# EXM_Relay_Three_-_Rev_A1.net
KiCad netlist of a schematic drawn in EAGLE
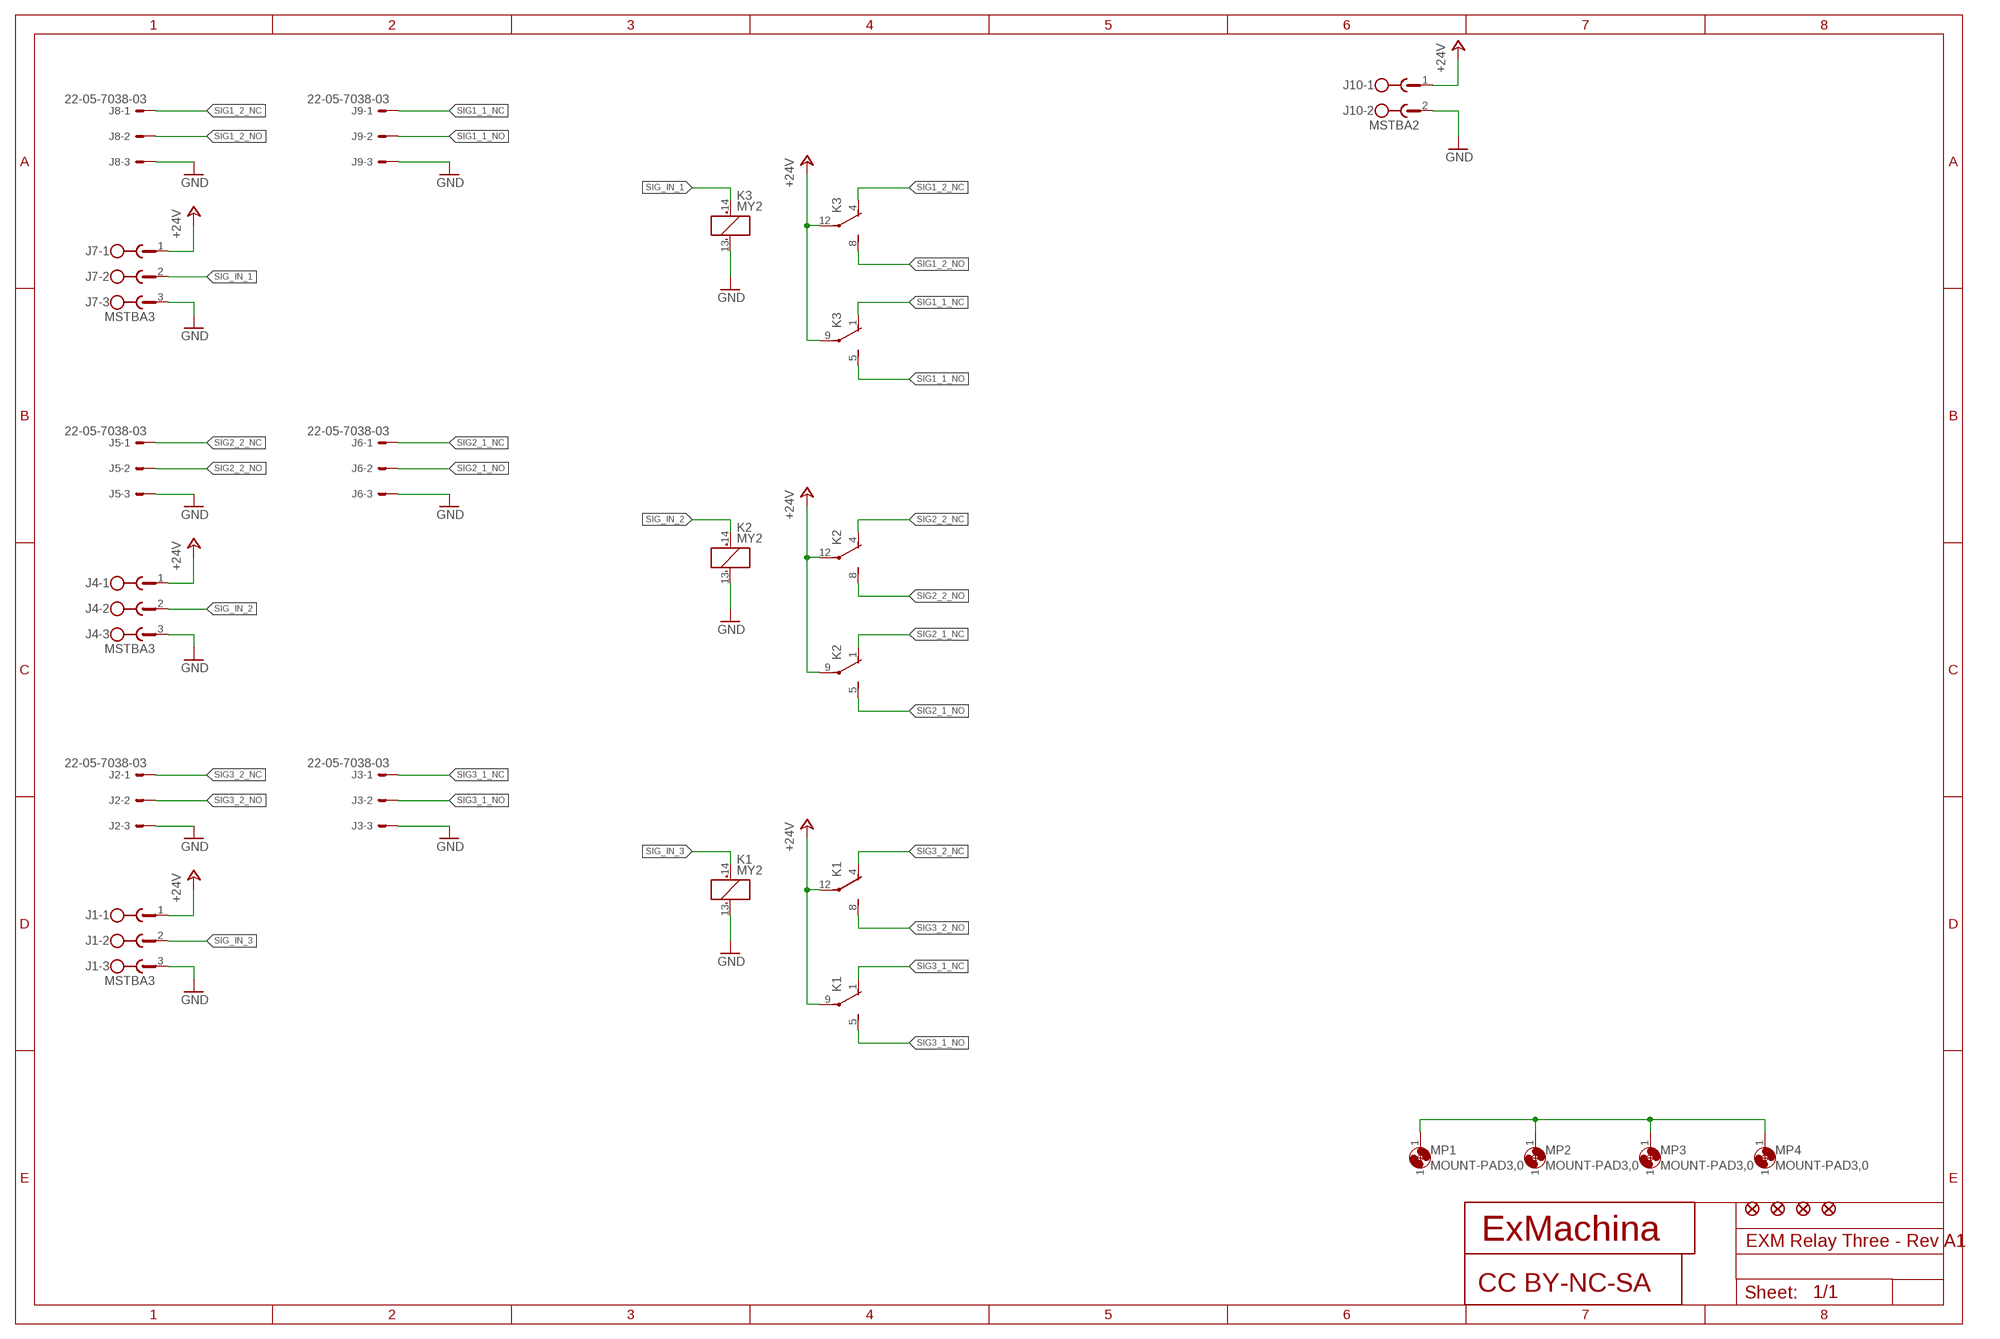
[diagram p0: schematic, sheet 1]

(export (version "E")
  (design (tool "Eeschema 10.0.6"))
  (components
    (comp (ref "CC1")
      (value "CC-BY-NC-SA")
      (footprint "eagle-import:CC-BY-NC-SA")
      (libsource (lib "eagle-import") (part "CC-BY-NC-SA"))
    )
    (comp (ref "J1")
      (value "MSTBA3")
      (footprint "eagle-import:MSTBA3")
      (fields (field (name "MF") "FARNELL") (field (name "MPN") "1757255"))
      (libsource (lib "eagle-import") (part "MSTBA3"))
    )
    (comp (ref "J2")
      (value "22-05-7038-03")
      (footprint "eagle-import:7395-03")
      (fields (field (name "MPN") "22-05-7038") (field (name "OC_NEWARK") "26M6362"))
      (libsource (lib "eagle-import") (part "22-?-0305-7038"))
    )
    (comp (ref "J3")
      (value "22-05-7038-03")
      (footprint "eagle-import:7395-03")
      (fields (field (name "MPN") "22-05-7038") (field (name "OC_NEWARK") "26M6362"))
      (libsource (lib "eagle-import") (part "22-?-0305-7038"))
    )
    (comp (ref "J4")
      (value "MSTBA3")
      (footprint "eagle-import:MSTBA3")
      (fields (field (name "MF") "FARNELL") (field (name "MPN") "1757255"))
      (libsource (lib "eagle-import") (part "MSTBA3"))
    )
    (comp (ref "J5")
      (value "22-05-7038-03")
      (footprint "eagle-import:7395-03")
      (fields (field (name "MPN") "22-05-7038") (field (name "OC_NEWARK") "26M6362"))
      (libsource (lib "eagle-import") (part "22-?-0305-7038"))
    )
    (comp (ref "J6")
      (value "22-05-7038-03")
      (footprint "eagle-import:7395-03")
      (fields (field (name "MPN") "22-05-7038") (field (name "OC_NEWARK") "26M6362"))
      (libsource (lib "eagle-import") (part "22-?-0305-7038"))
    )
    (comp (ref "J7")
      (value "MSTBA3")
      (footprint "eagle-import:MSTBA3")
      (fields (field (name "MF") "FARNELL") (field (name "MPN") "1757255"))
      (libsource (lib "eagle-import") (part "MSTBA3"))
    )
    (comp (ref "J8")
      (value "22-05-7038-03")
      (footprint "eagle-import:7395-03")
      (fields (field (name "MPN") "22-05-7038") (field (name "OC_NEWARK") "26M6362"))
      (libsource (lib "eagle-import") (part "22-?-0305-7038"))
    )
    (comp (ref "J9")
      (value "22-05-7038-03")
      (footprint "eagle-import:7395-03")
      (fields (field (name "MPN") "22-05-7038") (field (name "OC_NEWARK") "26M6362"))
      (libsource (lib "eagle-import") (part "22-?-0305-7038"))
    )
    (comp (ref "J10")
      (value "MSTBA2")
      (footprint "eagle-import:MSTBA2")
      (fields (field (name "MF") "FARNELL") (field (name "MPN") "1757242"))
      (libsource (lib "eagle-import") (part "MSTBA2"))
    )
    (comp (ref "JP1")
      (value "FIDUCIAL1X2")
      (footprint "eagle-import:FIDUCIAL-1X2")
      (libsource (lib "eagle-import") (part "FIDUCIAL1X2"))
    )
    (comp (ref "JP2")
      (value "FIDUCIAL1X2")
      (footprint "eagle-import:FIDUCIAL-1X2")
      (libsource (lib "eagle-import") (part "FIDUCIAL1X2"))
    )
    (comp (ref "JP3")
      (value "FIDUCIAL1X2")
      (footprint "eagle-import:FIDUCIAL-1X2")
      (libsource (lib "eagle-import") (part "FIDUCIAL1X2"))
    )
    (comp (ref "JP4")
      (value "FIDUCIAL1X2")
      (footprint "eagle-import:FIDUCIAL-1X2")
      (libsource (lib "eagle-import") (part "FIDUCIAL1X2"))
    )
    (comp (ref "K1")
      (value "MY2")
      (footprint "eagle-import:PY08")
      (fields
        (field (name "MF") "OMRON COMPONENTS USA")
        (field (name "MPN") "PY08")
        (field (name "OC_NEWARK") "36K3464")
      )
      (libsource (lib "eagle-import") (part "MY2"))
    )
    (comp (ref "K2")
      (value "MY2")
      (footprint "eagle-import:PY08")
      (fields
        (field (name "MF") "OMRON COMPONENTS USA")
        (field (name "MPN") "PY08")
        (field (name "OC_NEWARK") "36K3464")
      )
      (libsource (lib "eagle-import") (part "MY2"))
    )
    (comp (ref "K3")
      (value "MY2")
      (footprint "eagle-import:PY08")
      (fields
        (field (name "MF") "OMRON COMPONENTS USA")
        (field (name "MPN") "PY08")
        (field (name "OC_NEWARK") "36K3464")
      )
      (libsource (lib "eagle-import") (part "MY2"))
    )
    (comp (ref "MP1")
      (value "MOUNT-PAD3,0")
      (footprint "eagle-import:P3,0")
      (libsource (lib "eagle-import") (part "MOUNT-PAD3,0"))
    )
    (comp (ref "MP2")
      (value "MOUNT-PAD3,0")
      (footprint "eagle-import:P3,0")
      (libsource (lib "eagle-import") (part "MOUNT-PAD3,0"))
    )
    (comp (ref "MP3")
      (value "MOUNT-PAD3,0")
      (footprint "eagle-import:P3,0")
      (libsource (lib "eagle-import") (part "MOUNT-PAD3,0"))
    )
    (comp (ref "MP4")
      (value "MOUNT-PAD3,0")
      (footprint "eagle-import:P3,0")
      (libsource (lib "eagle-import") (part "MOUNT-PAD3,0"))
    )
    (comp (ref "T1")
      (value "EXMACHINA-LOGO-NAME")
      (footprint "eagle-import:EXM-LOGO-BASELINE")
      (libsource (lib "eagle-import") (part "EXMACHINA-LOGO-NAME"))
    )
  )
  (nets
    (net (code "1") (name "+24V") (class "Default")
      (node (ref "J1") (pin "1") (pinfunction "1_1") (pintype "passive"))
      (node (ref "J10") (pin "1") (pinfunction "1_1") (pintype "passive"))
      (node (ref "J4") (pin "1") (pinfunction "1_1") (pintype "passive"))
      (node (ref "J7") (pin "1") (pinfunction "1_1") (pintype "passive"))
      (node (ref "K1") (pin "12") (pinfunction "C_12") (pintype "passive"))
      (node (ref "K1") (pin "9") (pinfunction "C_9") (pintype "passive"))
      (node (ref "K2") (pin "12") (pinfunction "C_12") (pintype "passive"))
      (node (ref "K2") (pin "9") (pinfunction "C_9") (pintype "passive"))
      (node (ref "K3") (pin "12") (pinfunction "C_12") (pintype "passive"))
      (node (ref "K3") (pin "9") (pinfunction "C_9") (pintype "passive"))
    )
    (net (code "2") (name "GND") (class "Default")
      (node (ref "J1") (pin "3") (pinfunction "1_3") (pintype "passive"))
      (node (ref "J10") (pin "2") (pinfunction "1_2") (pintype "passive"))
      (node (ref "J2") (pin "3") (pinfunction "S_3") (pintype "passive"))
      (node (ref "J3") (pin "3") (pinfunction "S_3") (pintype "passive"))
      (node (ref "J4") (pin "3") (pinfunction "1_3") (pintype "passive"))
      (node (ref "J5") (pin "3") (pinfunction "S_3") (pintype "passive"))
      (node (ref "J6") (pin "3") (pinfunction "S_3") (pintype "passive"))
      (node (ref "J7") (pin "3") (pinfunction "1_3") (pintype "passive"))
      (node (ref "J8") (pin "3") (pinfunction "S_3") (pintype "passive"))
      (node (ref "J9") (pin "3") (pinfunction "S_3") (pintype "passive"))
      (node (ref "K1") (pin "13") (pinfunction "-_13") (pintype "passive"))
      (node (ref "K2") (pin "13") (pinfunction "-_13") (pintype "passive"))
      (node (ref "K3") (pin "13") (pinfunction "-_13") (pintype "passive"))
    )
    (net (code "3") (name "MOUNT-PAD3,0") (class "Default")
      (node (ref "MP1") (pin "1") (pinfunction "1_1") (pintype "power_in"))
      (node (ref "MP2") (pin "1") (pinfunction "1_1") (pintype "power_in"))
      (node (ref "MP3") (pin "1") (pinfunction "1_1") (pintype "power_in"))
      (node (ref "MP4") (pin "1") (pinfunction "1_1") (pintype "power_in"))
    )
    (net (code "4") (name "SIG1_1_NC") (class "Default")
      (node (ref "J9") (pin "1") (pinfunction "S_1") (pintype "passive"))
      (node (ref "K3") (pin "1") (pinfunction "NC_1") (pintype "passive"))
    )
    (net (code "5") (name "SIG1_1_NO") (class "Default")
      (node (ref "J9") (pin "2") (pinfunction "S_2") (pintype "passive"))
      (node (ref "K3") (pin "5") (pinfunction "NO_5") (pintype "passive"))
    )
    (net (code "6") (name "SIG1_2_NC") (class "Default")
      (node (ref "J8") (pin "1") (pinfunction "S_1") (pintype "passive"))
      (node (ref "K3") (pin "4") (pinfunction "NC_4") (pintype "passive"))
    )
    (net (code "7") (name "SIG1_2_NO") (class "Default")
      (node (ref "J8") (pin "2") (pinfunction "S_2") (pintype "passive"))
      (node (ref "K3") (pin "8") (pinfunction "NO_8") (pintype "passive"))
    )
    (net (code "8") (name "SIG2_1_NC") (class "Default")
      (node (ref "J6") (pin "1") (pinfunction "S_1") (pintype "passive"))
      (node (ref "K2") (pin "1") (pinfunction "NC_1") (pintype "passive"))
    )
    (net (code "9") (name "SIG2_1_NO") (class "Default")
      (node (ref "J6") (pin "2") (pinfunction "S_2") (pintype "passive"))
      (node (ref "K2") (pin "5") (pinfunction "NO_5") (pintype "passive"))
    )
    (net (code "10") (name "SIG2_2_NC") (class "Default")
      (node (ref "J5") (pin "1") (pinfunction "S_1") (pintype "passive"))
      (node (ref "K2") (pin "4") (pinfunction "NC_4") (pintype "passive"))
    )
    (net (code "11") (name "SIG2_2_NO") (class "Default")
      (node (ref "J5") (pin "2") (pinfunction "S_2") (pintype "passive"))
      (node (ref "K2") (pin "8") (pinfunction "NO_8") (pintype "passive"))
    )
    (net (code "12") (name "SIG3_1_NC") (class "Default")
      (node (ref "J3") (pin "1") (pinfunction "S_1") (pintype "passive"))
      (node (ref "K1") (pin "1") (pinfunction "NC_1") (pintype "passive"))
    )
    (net (code "13") (name "SIG3_1_NO") (class "Default")
      (node (ref "J3") (pin "2") (pinfunction "S_2") (pintype "passive"))
      (node (ref "K1") (pin "5") (pinfunction "NO_5") (pintype "passive"))
    )
    (net (code "14") (name "SIG3_2_NC") (class "Default")
      (node (ref "J2") (pin "1") (pinfunction "S_1") (pintype "passive"))
      (node (ref "K1") (pin "4") (pinfunction "NC_4") (pintype "passive"))
    )
    (net (code "15") (name "SIG3_2_NO") (class "Default")
      (node (ref "J2") (pin "2") (pinfunction "S_2") (pintype "passive"))
      (node (ref "K1") (pin "8") (pinfunction "NO_8") (pintype "passive"))
    )
    (net (code "16") (name "SIG_IN_1") (class "Default")
      (node (ref "J7") (pin "2") (pinfunction "1_2") (pintype "passive"))
      (node (ref "K3") (pin "14") (pinfunction "+_14") (pintype "passive"))
    )
    (net (code "17") (name "SIG_IN_2") (class "Default")
      (node (ref "J4") (pin "2") (pinfunction "1_2") (pintype "passive"))
      (node (ref "K2") (pin "14") (pinfunction "+_14") (pintype "passive"))
    )
    (net (code "18") (name "SIG_IN_3") (class "Default")
      (node (ref "J1") (pin "2") (pinfunction "1_2") (pintype "passive"))
      (node (ref "K1") (pin "14") (pinfunction "+_14") (pintype "passive"))
    )
  )
)
